# LPCB219_-_LASER_CHANNEL.net
KiCad netlist of a schematic drawn in Altium Designer
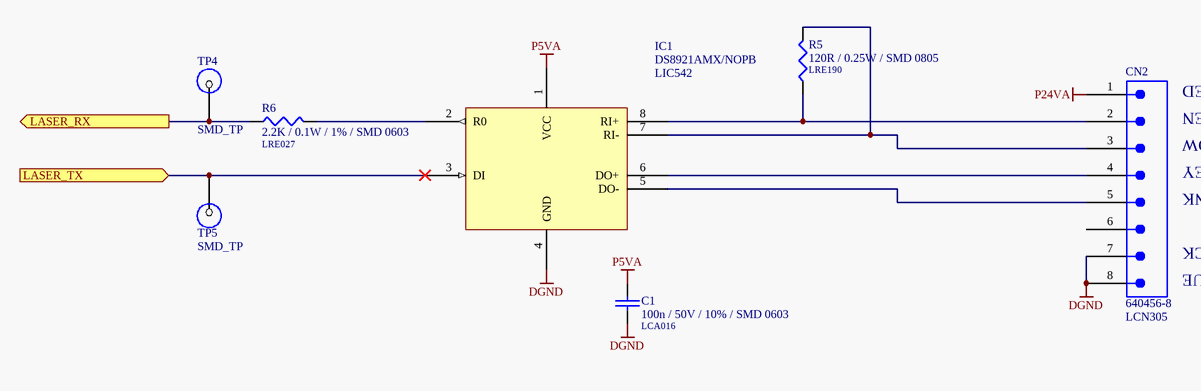
[diagram p0: LPCB219 - LASER CHANNEL.SchDoc]

(export (version "E")
  (design (tool "Eeschema 10.0.6"))
  (components
    (comp (ref "C1")
      (value "100n / 50V / 10% / SMD 0603")
      (footprint "LFP011__CC1608-0603-IPC7351_B")
      (description "Capacitor, Ceramic Chip, 100nF (0.1uF), 50V, 5%, SMD 0603 [LCA016]")
      (fields (field (name "LDL_NUMBER") "LCA016"))
      (libsource (lib "LDL_Capacitors") (part "100n / 50V / 10% / SMD 0603"))
    )
    (comp (ref "CN2")
      (value "640456-8")
      (footprint "640456-8")
      (description "Connector, Male Header, 8 Way")
      (fields (field (name "LDL_NUMBER") "LCN305"))
      (libsource (lib "LDL_Connectors") (part "640456-8"))
    )
    (comp (ref "IC1")
      (value "DS8921AMX/NOPB")
      (footprint "LFP069__R-8G")
      (description "IC, RS422 Tx Rx, SMD SOIC 8")
      (fields (field (name "LDL_NUMBER") "LIC542"))
      (libsource (lib "LDL_Semiconductors") (part "DS8921AMX/NOPB"))
    )
    (comp (ref "R5")
      (value "120R / 0.25W / SMD 0805")
      (footprint "LFP029__CR2012-0805")
      (description "Resistor, Thick Film, 120R, 0.25W, 5%, SMD 0805 [LRE190]")
      (fields (field (name "LDL_NUMBER") "LRE190"))
      (libsource (lib "LDL_Resistors") (part "120R / 0.25W / SMD 0805"))
    )
    (comp (ref "R6")
      (value "2.2K / 0.1W / 1% / SMD 0603")
      (footprint "LFP020__CR1608-0603-IPC7351_B")
      (description "Resistor, Ceramic Chip, 2.2K, 0.1W, 1%, SMD 0603 [LRE027]")
      (fields (field (name "LDL_NUMBER") "LRE027"))
      (libsource (lib "LDL_Resistors") (part "2.2K / 0.1W / 1% / SMD 0603"))
    )
    (comp (ref "TP4")
      (value "SMD_TP")
      (footprint "SMD-TP")
      (description "SMD Test Point")
      (libsource (lib "LDL_Connectors") (part "SMD_TP"))
    )
    (comp (ref "TP5")
      (value "SMD_TP")
      (footprint "SMD-TP")
      (description "SMD Test Point")
      (libsource (lib "LDL_Connectors") (part "SMD_TP"))
    )
  )
  (nets
    (net (code "1") (name "/LASER_RX") (class "Default")
      (node (ref "R6") (pin "1") (pintype "passive"))
      (node (ref "TP4") (pin "1") (pintype "passive"))
    )
    (net (code "2") (name "/LASER_TX") (class "Default")
      (node (ref "IC1") (pin "3") (pinfunction "DI_3") (pintype "input"))
      (node (ref "TP5") (pin "1") (pintype "passive"))
    )
    (net (code "3") (name "DGND") (class "Default")
      (node (ref "C1") (pin "2") (pintype "passive"))
      (node (ref "CN2") (pin "7") (pinfunction "7_7") (pintype "passive"))
      (node (ref "CN2") (pin "8") (pinfunction "8_8") (pintype "passive"))
      (node (ref "IC1") (pin "4") (pinfunction "GND_4") (pintype "power_in"))
    )
    (net (code "4") (name "Net-(IC1-DO+)") (class "Default")
      (node (ref "CN2") (pin "4") (pinfunction "4_4") (pintype "passive"))
      (node (ref "IC1") (pin "6") (pinfunction "DO+_6") (pintype "passive"))
    )
    (net (code "5") (name "Net-(IC1-DO-)") (class "Default")
      (node (ref "CN2") (pin "5") (pinfunction "5_5") (pintype "passive"))
      (node (ref "IC1") (pin "5") (pinfunction "DO-_5") (pintype "passive"))
    )
    (net (code "6") (name "Net-(IC1-R0)") (class "Default")
      (node (ref "IC1") (pin "2") (pinfunction "R0_2") (pintype "output"))
      (node (ref "R6") (pin "2") (pintype "passive"))
    )
    (net (code "7") (name "Net-(IC1-RI+)") (class "Default")
      (node (ref "CN2") (pin "2") (pinfunction "2_2") (pintype "passive"))
      (node (ref "IC1") (pin "8") (pinfunction "RI+_8") (pintype "passive"))
      (node (ref "R5") (pin "1") (pintype "passive"))
    )
    (net (code "8") (name "Net-(IC1-RI-)") (class "Default")
      (node (ref "CN2") (pin "3") (pinfunction "3_3") (pintype "passive"))
      (node (ref "IC1") (pin "7") (pinfunction "RI-_7") (pintype "passive"))
      (node (ref "R5") (pin "2") (pintype "passive"))
    )
    (net (code "9") (name "P5VA") (class "Default")
      (node (ref "C1") (pin "1") (pintype "passive"))
      (node (ref "IC1") (pin "1") (pinfunction "VCC_1") (pintype "power_in"))
    )
    (net (code "10") (name "P24VA") (class "Default")
      (node (ref "CN2") (pin "1") (pinfunction "1_1") (pintype "passive"))
    )
    (net (code "11") (name "unconnected-(CN2-Pad6)") (class "Default")
      (node (ref "CN2") (pin "6") (pinfunction "6_6") (pintype "passive"))
    )
  )
)
